# circuito.net
KiCad netlist of a schematic drawn in EAGLE
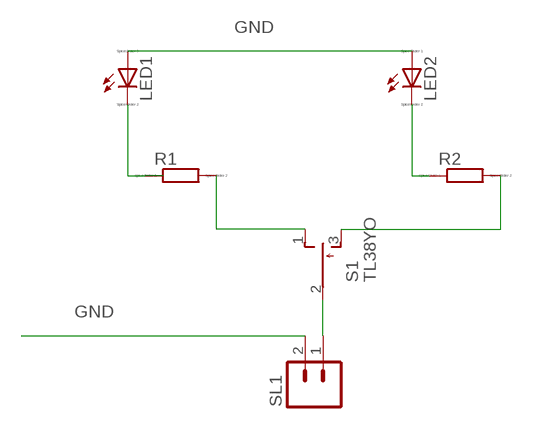
[diagram p0: schematic, sheet 1]

(export (version "E")
  (design (tool "Eeschema 10.0.6"))
  (components
    (comp (ref "LED1")
      (value "LED_ELD260")
      (footprint "eagle-import:LED_LD260")
      (libsource (lib "eagle-import") (part "LED_ELD260"))
    )
    (comp (ref "LED2")
      (value "LED_ELD260")
      (footprint "eagle-import:LED_LD260")
      (libsource (lib "eagle-import") (part "LED_ELD260"))
    )
    (comp (ref "R1")
      (value "R0204/7")
      (footprint "eagle-import:0204_7")
      (libsource (lib "eagle-import") (part "R0204/7"))
    )
    (comp (ref "R2")
      (value "R0204/7")
      (footprint "eagle-import:0204_7")
      (libsource (lib "eagle-import") (part "R0204/7"))
    )
    (comp (ref "S1")
      (value "TL38YO")
      (footprint "eagle-import:TL3XYO")
      (libsource (lib "eagle-import") (part "TL38YO"))
    )
    (comp (ref "SL1")
      (value "M02")
      (footprint "eagle-import:02P")
      (libsource (lib "eagle-import") (part "M02"))
    )
  )
  (nets
    (net (code "1") (name "/GND") (class "Default")
      (node (ref "LED1") (pin "A") (pinfunction "A_A") (pintype "passive"))
      (node (ref "LED2") (pin "A") (pinfunction "A_A") (pintype "passive"))
      (node (ref "SL1") (pin "2") (pinfunction "2_2") (pintype "passive"))
    )
    (net (code "2") (name "Net-(LED1-C)") (class "Default")
      (node (ref "LED1") (pin "K") (pinfunction "C_K") (pintype "passive"))
      (node (ref "R1") (pin "1") (pinfunction "1_1") (pintype "passive"))
    )
    (net (code "3") (name "Net-(LED2-C)") (class "Default")
      (node (ref "LED2") (pin "K") (pinfunction "C_K") (pintype "passive"))
      (node (ref "R2") (pin "1") (pinfunction "1_1") (pintype "passive"))
    )
    (net (code "4") (name "Net-(S1-O)") (class "Default")
      (node (ref "R1") (pin "2") (pinfunction "2_2") (pintype "passive"))
      (node (ref "S1") (pin "1") (pinfunction "O_1") (pintype "passive"))
    )
    (net (code "5") (name "Net-(S1-P)") (class "Default")
      (node (ref "S1") (pin "2") (pinfunction "P_2") (pintype "passive"))
      (node (ref "SL1") (pin "1") (pinfunction "1_1") (pintype "passive"))
    )
    (net (code "6") (name "Net-(S1-S)") (class "Default")
      (node (ref "R2") (pin "2") (pinfunction "2_2") (pintype "passive"))
      (node (ref "S1") (pin "3") (pinfunction "S_3") (pintype "passive"))
    )
  )
)
